# Motor-Z.net
KiCad netlist of a schematic drawn in Altium Designer
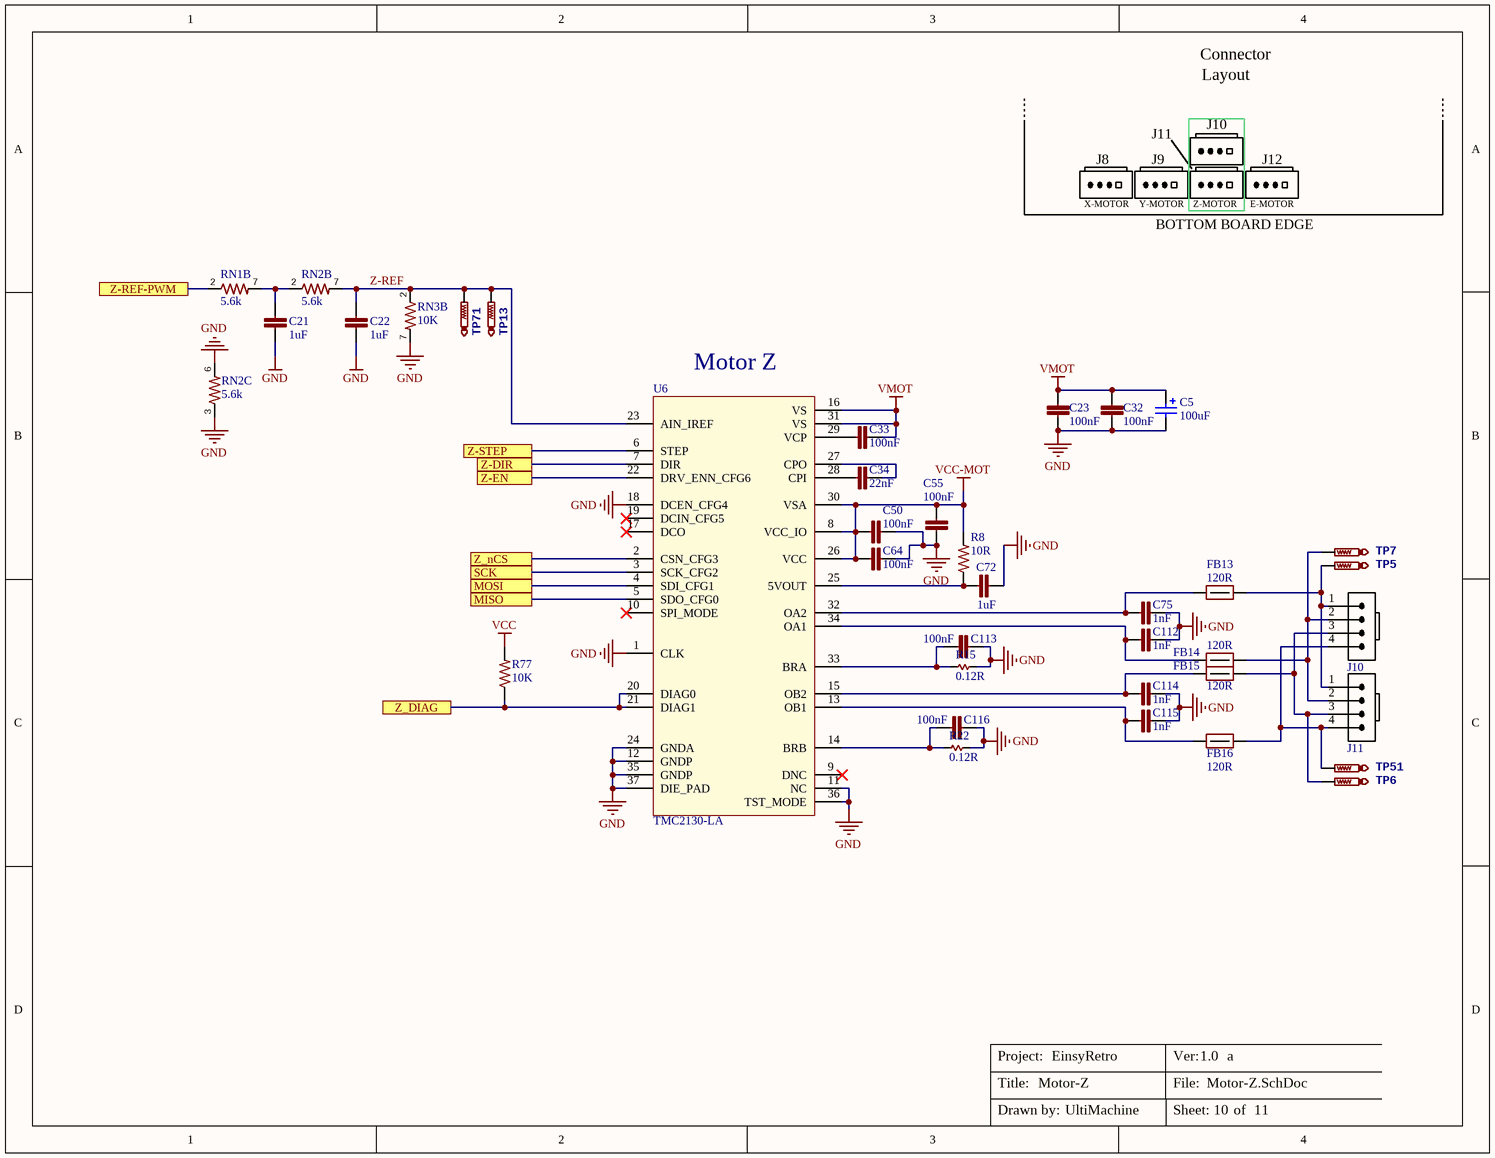
[diagram p0: Motor-Z.SchDoc]

(export (version "E")
  (design (tool "Eeschema 10.0.6"))
  (components
    (comp (ref "C5")
      (value "100uF")
      (footprint "CAP-ELEC-063063077")
      (description "CAP ALUM 100UF 35V 20% SMD")
      (fields (field (name "MANUFACTURER") "Nichicon") (field (name "TOLERANCE") "+/- 20%"))
      (libsource (lib "3Delight") (part "UWT1V101MCL1GS"))
    )
    (comp (ref "C21")
      (value "1uF")
      (footprint "C0402")
      (description "CAP CER 0402 1uF 6.3V 10% X5R")
      (fields (field (name "MANUFACTURER") "Murata") (field (name "TOLERANCE") "+/- 10%"))
      (libsource (lib "3Delight") (part "GRM155R60J105KE19D"))
    )
    (comp (ref "C22")
      (value "1uF")
      (footprint "C0402")
      (description "CAP CER 0402 1uF 6.3V 10% X5R")
      (fields (field (name "MANUFACTURER") "Murata") (field (name "TOLERANCE") "+/- 10%"))
      (libsource (lib "3Delight") (part "GRM155R60J105KE19D"))
    )
    (comp (ref "C23")
      (value "100nF")
      (footprint "C0603")
      (description "CAP CER 0603 100nF 50V 10% X7R")
      (fields (field (name "MANUFACTURER") "Kemet") (field (name "TOLERANCE") "+/- 10%"))
      (libsource (lib "") (part "C0603C104K5RACTU_1"))
    )
    (comp (ref "C32")
      (value "100nF")
      (footprint "C0603")
      (description "CAP CER 0603 100nF 50V 10% X7R")
      (fields (field (name "MANUFACTURER") "Kemet") (field (name "TOLERANCE") "+/- 10%"))
      (libsource (lib "") (part "C0603C104K5RACTU_1"))
    )
    (comp (ref "C33")
      (value "100nF")
      (footprint "C0603")
      (description "CAP CER 0603 100nF 50V 10% X7R")
      (fields (field (name "MANUFACTURER") "Kemet") (field (name "TOLERANCE") "+/- 10%"))
      (libsource (lib "") (part "C0603C104K5RACTU_2"))
    )
    (comp (ref "C34")
      (value "22nF")
      (footprint "C0402")
      (description "CAP CER 0402 22nF ±10% 50V X7R")
      (fields (field (name "MANUFACTURER") "YAGEO") (field (name "TOLERANCE") "+/- 10%"))
      (libsource (lib "3Delight") (part "GCM155R71H223KA55D"))
    )
    (comp (ref "C50")
      (value "100nF")
      (footprint "C0402")
      (description "CAP CER 0402 100nF 16V 10% X7R")
      (fields (field (name "MANUFACTURER") "Murata") (field (name "TOLERANCE") "+/- 10%"))
      (libsource (lib "") (part "GRM155R71C104KA88D_1"))
    )
    (comp (ref "C55")
      (value "100nF")
      (footprint "C0402")
      (description "CAP CER 0402 100nF 16V 10% X7R")
      (fields (field (name "MANUFACTURER") "Murata") (field (name "TOLERANCE") "+/- 10%"))
      (libsource (lib "3Delight") (part "GRM155R71C104KA88D"))
    )
    (comp (ref "C64")
      (value "100nF")
      (footprint "C0402")
      (description "CAP CER 0402 100nF 16V 10% X7R")
      (fields (field (name "MANUFACTURER") "Murata") (field (name "TOLERANCE") "+/- 10%"))
      (libsource (lib "") (part "GRM155R71C104KA88D_1"))
    )
    (comp (ref "C72")
      (value "1uF")
      (footprint "C0402")
      (description "CAP CER 0402 1uF 6.3V 10% X5R")
      (fields (field (name "MANUFACTURER") "Murata") (field (name "TOLERANCE") "+/- 10%"))
      (libsource (lib "") (part "GRM155R60J105KE19D_1"))
    )
    (comp (ref "C75")
      (value "1nF")
      (footprint "C0603")
      (description "CAP CER 0603  1nF 50v 10% X7R")
      (fields (field (name "MANUFACTURER") "Kemet") (field (name "TOLERANCE") "+/- 10%"))
      (libsource (lib "3Delight") (part "C0603C102K5RACTU"))
    )
    (comp (ref "C112")
      (value "1nF")
      (footprint "C0603")
      (description "CAP CER 0603  1nF 50v 10% X7R")
      (fields (field (name "MANUFACTURER") "Kemet") (field (name "TOLERANCE") "+/- 10%"))
      (libsource (lib "3Delight") (part "C0603C102K5RACTU"))
    )
    (comp (ref "C113")
      (value "100nF")
      (footprint "C0603")
      (description "CAP CER 0603 100nF 50V 10% X7R")
      (fields (field (name "MANUFACTURER") "Kemet") (field (name "TOLERANCE") "+/- 10%"))
      (libsource (lib "3Delight") (part "C0603C104K5RACTU"))
    )
    (comp (ref "C114")
      (value "1nF")
      (footprint "C0603")
      (description "CAP CER 0603  1nF 50v 10% X7R")
      (fields (field (name "MANUFACTURER") "Kemet") (field (name "TOLERANCE") "+/- 10%"))
      (libsource (lib "3Delight") (part "C0603C102K5RACTU"))
    )
    (comp (ref "C115")
      (value "1nF")
      (footprint "C0603")
      (description "CAP CER 0603  1nF 50v 10% X7R")
      (fields (field (name "MANUFACTURER") "Kemet") (field (name "TOLERANCE") "+/- 10%"))
      (libsource (lib "3Delight") (part "C0603C102K5RACTU"))
    )
    (comp (ref "C116")
      (value "100nF")
      (footprint "C0603")
      (description "CAP CER 0603 100nF 50V 10% X7R")
      (fields (field (name "MANUFACTURER") "Kemet") (field (name "TOLERANCE") "+/- 10%"))
      (libsource (lib "3Delight") (part "C0603C104K5RACTU"))
    )
    (comp (ref "FB13")
      (value "120R")
      (footprint "FB0603")
      (description "FERRITE BEAD 120 OHM 0603 1LN")
      (fields (field (name "MANUFACTURER") "Samsung") (field (name "PART") "FERRITE 120R 3A 0603"))
      (libsource (lib "Inductors") (part "FERRITE 120R 3A 0603"))
    )
    (comp (ref "FB14")
      (value "120R")
      (footprint "FB0603")
      (description "FERRITE BEAD 120 OHM 0603 1LN")
      (fields (field (name "MANUFACTURER") "Samsung") (field (name "PART") "FERRITE 120R 3A 0603"))
      (libsource (lib "Inductors") (part "FERRITE 120R 3A 0603"))
    )
    (comp (ref "FB15")
      (value "120R")
      (footprint "FB0603")
      (description "FERRITE BEAD 120 OHM 0603 1LN")
      (fields (field (name "MANUFACTURER") "Samsung") (field (name "PART") "FERRITE 120R 3A 0603"))
      (libsource (lib "Inductors") (part "FERRITE 120R 3A 0603"))
    )
    (comp (ref "FB16")
      (value "120R")
      (footprint "FB0603")
      (description "FERRITE BEAD 120 OHM 0603 1LN")
      (fields (field (name "MANUFACTURER") "Samsung") (field (name "PART") "FERRITE 120R 3A 0603"))
      (libsource (lib "Inductors") (part "FERRITE 120R 3A 0603"))
    )
    (comp (ref "J10")
      (value "Molex 0705430003")
      (footprint "4POL254 PIN-IN-PASTE")
      (description "Molex 4 Pin Clip Connector - Pin In Paste footprint")
      (libsource (lib "Connectors") (part "Molex 0705430003 PIP"))
    )
    (comp (ref "J11")
      (value "Molex 0705430003")
      (footprint "4POL254 PIN-IN-PASTE")
      (description "Molex 4 Pin Clip Connector - Pin In Paste footprint")
      (libsource (lib "Connectors") (part "Molex 0705430003 PIP"))
    )
    (comp (ref "R8")
      (value "10R")
      (footprint "R0402")
      (description "RES SMD 10 OHM 1% 1/16W 0402")
      (fields (field (name "MANUFACTURER") "Yageo") (field (name "TOLERANCE") "+/- 1%"))
      (libsource (lib "3Delight") (part "RC0402FR-0710RL"))
    )
    (comp (ref "R15")
      (value "0.12R")
      (footprint "R1206")
      (description "RES 0.12 OHM 1% 1/2W 1206")
      (fields (field (name "TOLERANCE") "+/- 1%"))
      (libsource (lib "Resistors") (part "0.12R 1% 1206"))
    )
    (comp (ref "R22")
      (value "0.12R")
      (footprint "R1206")
      (description "RES 0.12 OHM 1% 1/2W 1206")
      (fields (field (name "TOLERANCE") "+/- 1%"))
      (libsource (lib "Resistors") (part "0.12R 1% 1206"))
    )
    (comp (ref "R77")
      (value "10K")
      (footprint "R0402")
      (description "RES SMD 10K OHM 1% 1/16W 0402")
      (fields (field (name "MANUFACTURER") "Yageo") (field (name "PART") "10k 1% 0402"))
      (libsource (lib "3Delight") (part "RC0402FR-0710KP"))
    )
    (comp (ref "RN1")
      (value "5.6k")
      (footprint "CAY16")
      (description "RES ARRAY 4 RES 5.6K OHM 1206")
      (fields (field (name "MANUFACTURER") "Bourns") (field (name "TOLERANCE") "+/- 5%"))
      (libsource (lib "Resistors") (part "5.6k x 4 5% 1206"))
    )
    (comp (ref "RN2")
      (value "5.6k")
      (footprint "CAY16")
      (description "RES ARRAY 4 RES 5.6K OHM 1206")
      (fields (field (name "MANUFACTURER") "Bourns") (field (name "TOLERANCE") "+/- 5%"))
      (libsource (lib "Resistors") (part "5.6k x 4 5% 1206"))
    )
    (comp (ref "RN3")
      (value "10K")
      (footprint "CAY16")
      (description "RES ARRAY 4 RES 10K 1206 62.5mW 5%")
      (fields (field (name "MANUFACTURER") "Bourns") (field (name "TOLERANCE") "+/- 5%"))
      (libsource (lib "3Delight") (part "CAY16-103J4LF"))
    )
    (comp (ref "TP5")
      (value "TestPoint")
      (footprint "TP1-27")
      (description "Test Point")
      (libsource (lib "3Delight") (part "TestPoint"))
    )
    (comp (ref "TP6")
      (value "TestPoint")
      (footprint "TP1-27")
      (description "Test Point")
      (libsource (lib "3Delight") (part "TestPoint"))
    )
    (comp (ref "TP7")
      (value "TestPoint")
      (footprint "TP1-27")
      (description "Test Point")
      (libsource (lib "3Delight") (part "TestPoint"))
    )
    (comp (ref "TP13")
      (value "TestPoint")
      (footprint "TP1-27")
      (description "Test Point")
      (libsource (lib "") (part "TestPoint_1"))
    )
    (comp (ref "TP51")
      (value "TestPoint")
      (footprint "TP1-27")
      (description "Test Point")
      (libsource (lib "3Delight") (part "TestPoint"))
    )
    (comp (ref "TP71")
      (value "TestPoint")
      (footprint "TP1-27")
      (description "Test Point")
      (libsource (lib "") (part "TestPoint_1"))
    )
    (comp (ref "U6")
      (value "TMC2130-LA")
      (footprint "QFN36-50P500X600X900_HS-37N")
      (description "IC STEPPER MOTOR DVR SPI 36QFN")
      (fields (field (name "MANUFACTURER") "Trinamic") (field (name "PART") "TMC2130"))
      (libsource (lib "3Delight") (part "TMC2130-LA-T"))
    )
  )
  (nets
    (net (code "1") (name "/MISO") (class "Default")
      (node (ref "U6") (pin "5") (pinfunction "SDO_CFG0_5") (pintype "passive"))
    )
    (net (code "2") (name "/MOSI") (class "Default")
      (node (ref "U6") (pin "4") (pinfunction "SDI_CFG1_4") (pintype "passive"))
    )
    (net (code "3") (name "/SCK") (class "Default")
      (node (ref "U6") (pin "3") (pinfunction "SCK_CFG2_3") (pintype "passive"))
    )
    (net (code "4") (name "/Z-DIR") (class "Default")
      (node (ref "U6") (pin "7") (pinfunction "DIR_7") (pintype "passive"))
    )
    (net (code "5") (name "/Z-EN") (class "Default")
      (node (ref "U6") (pin "22") (pinfunction "DRV_ENN_CFG6_22") (pintype "passive"))
    )
    (net (code "6") (name "/Z-REF") (class "Default")
      (node (ref "C22") (pin "1") (pinfunction "1_1") (pintype "passive"))
      (node (ref "RN2") (pin "7") (pinfunction "2_7") (pintype "passive"))
      (node (ref "RN3") (pin "2") (pinfunction "1_2") (pintype "passive"))
      (node (ref "TP13") (pin "TP") (pinfunction "TP_TP") (pintype "passive"))
      (node (ref "TP71") (pin "TP") (pinfunction "TP_TP") (pintype "passive"))
      (node (ref "U6") (pin "23") (pinfunction "AIN_IREF_23") (pintype "passive"))
    )
    (net (code "7") (name "/Z-REF-PWM") (class "Default")
      (node (ref "RN1") (pin "2") (pinfunction "1_2") (pintype "passive"))
    )
    (net (code "8") (name "/Z-STEP") (class "Default")
      (node (ref "U6") (pin "6") (pinfunction "STEP_6") (pintype "passive"))
    )
    (net (code "9") (name "/Z_DIAG") (class "Default")
      (node (ref "R77") (pin "1") (pinfunction "1_1") (pintype "passive"))
      (node (ref "U6") (pin "20") (pinfunction "DIAG0_20") (pintype "passive"))
      (node (ref "U6") (pin "21") (pinfunction "DIAG1_21") (pintype "passive"))
    )
    (net (code "10") (name "/Z_nCS") (class "Default")
      (node (ref "U6") (pin "2") (pinfunction "CSN_CFG3_2") (pintype "passive"))
    )
    (net (code "11") (name "GND") (class "Default")
      (node (ref "C112") (pin "2") (pinfunction "2_2") (pintype "passive"))
      (node (ref "C113") (pin "1") (pinfunction "1_1") (pintype "passive"))
      (node (ref "C114") (pin "2") (pinfunction "2_2") (pintype "passive"))
      (node (ref "C115") (pin "2") (pinfunction "2_2") (pintype "passive"))
      (node (ref "C116") (pin "1") (pinfunction "1_1") (pintype "passive"))
      (node (ref "C21") (pin "2") (pinfunction "2_2") (pintype "passive"))
      (node (ref "C22") (pin "2") (pinfunction "2_2") (pintype "passive"))
      (node (ref "C23") (pin "1") (pinfunction "1_1") (pintype "passive"))
      (node (ref "C32") (pin "1") (pinfunction "1_1") (pintype "passive"))
      (node (ref "C5") (pin "2") (pinfunction "2_2") (pintype "passive"))
      (node (ref "C50") (pin "1") (pinfunction "1_1") (pintype "passive"))
      (node (ref "C55") (pin "1") (pinfunction "1_1") (pintype "passive"))
      (node (ref "C64") (pin "1") (pinfunction "1_1") (pintype "passive"))
      (node (ref "C72") (pin "2") (pinfunction "2_2") (pintype "passive"))
      (node (ref "C75") (pin "2") (pinfunction "2_2") (pintype "passive"))
      (node (ref "R15") (pin "2") (pinfunction "2_2") (pintype "passive"))
      (node (ref "R22") (pin "2") (pinfunction "2_2") (pintype "passive"))
      (node (ref "RN2") (pin "3") (pinfunction "1_3") (pintype "passive"))
      (node (ref "RN2") (pin "6") (pinfunction "2_6") (pintype "passive"))
      (node (ref "RN3") (pin "7") (pinfunction "2_7") (pintype "passive"))
      (node (ref "U6") (pin "1") (pinfunction "CLK_1") (pintype "passive"))
      (node (ref "U6") (pin "11") (pinfunction "NC_11") (pintype "passive"))
      (node (ref "U6") (pin "12") (pinfunction "GNDP_12") (pintype "passive"))
      (node (ref "U6") (pin "18") (pinfunction "DCEN_CFG4_18") (pintype "passive"))
      (node (ref "U6") (pin "24") (pinfunction "GNDA_24") (pintype "passive"))
      (node (ref "U6") (pin "35") (pinfunction "GNDP_35") (pintype "passive"))
      (node (ref "U6") (pin "36") (pinfunction "TST_MODE_36") (pintype "passive"))
      (node (ref "U6") (pin "37") (pinfunction "DIE_PAD_37") (pintype "passive"))
    )
    (net (code "12") (name "Net-(FB13-Pad2)") (class "Default")
      (node (ref "FB13") (pin "2") (pinfunction "2_2") (pintype "passive"))
      (node (ref "J10") (pin "1") (pinfunction "1_1") (pintype "passive"))
      (node (ref "J11") (pin "1") (pinfunction "1_1") (pintype "passive"))
      (node (ref "TP5") (pin "TP") (pinfunction "TP_TP") (pintype "passive"))
    )
    (net (code "13") (name "Net-(FB14-Pad2)") (class "Default")
      (node (ref "FB14") (pin "2") (pinfunction "2_2") (pintype "passive"))
      (node (ref "J10") (pin "2") (pinfunction "2_2") (pintype "passive"))
      (node (ref "J11") (pin "2") (pinfunction "2_2") (pintype "passive"))
      (node (ref "TP7") (pin "TP") (pinfunction "TP_TP") (pintype "passive"))
    )
    (net (code "14") (name "Net-(FB15-Pad2)") (class "Default")
      (node (ref "FB15") (pin "2") (pinfunction "2_2") (pintype "passive"))
      (node (ref "J10") (pin "3") (pinfunction "3_3") (pintype "passive"))
      (node (ref "J11") (pin "3") (pinfunction "3_3") (pintype "passive"))
      (node (ref "TP6") (pin "TP") (pinfunction "TP_TP") (pintype "passive"))
    )
    (net (code "15") (name "Net-(FB16-Pad2)") (class "Default")
      (node (ref "FB16") (pin "2") (pinfunction "2_2") (pintype "passive"))
      (node (ref "J10") (pin "4") (pinfunction "4_4") (pintype "passive"))
      (node (ref "J11") (pin "4") (pinfunction "4_4") (pintype "passive"))
      (node (ref "TP51") (pin "TP") (pinfunction "TP_TP") (pintype "passive"))
    )
    (net (code "16") (name "Net-(RN1B-2)") (class "Default")
      (node (ref "C21") (pin "1") (pinfunction "1_1") (pintype "passive"))
      (node (ref "RN1") (pin "7") (pinfunction "2_7") (pintype "passive"))
      (node (ref "RN2") (pin "2") (pinfunction "1_2") (pintype "passive"))
    )
    (net (code "17") (name "Net-(U6-5VOUT)") (class "Default")
      (node (ref "C72") (pin "1") (pinfunction "1_1") (pintype "passive"))
      (node (ref "R8") (pin "1") (pinfunction "1_1") (pintype "passive"))
      (node (ref "U6") (pin "25") (pinfunction "5VOUT_25") (pintype "passive"))
    )
    (net (code "18") (name "Net-(U6-BRA)") (class "Default")
      (node (ref "C113") (pin "2") (pinfunction "2_2") (pintype "passive"))
      (node (ref "R15") (pin "1") (pinfunction "1_1") (pintype "passive"))
      (node (ref "U6") (pin "33") (pinfunction "BRA_33") (pintype "passive"))
    )
    (net (code "19") (name "Net-(U6-BRB)") (class "Default")
      (node (ref "C116") (pin "2") (pinfunction "2_2") (pintype "passive"))
      (node (ref "R22") (pin "1") (pinfunction "1_1") (pintype "passive"))
      (node (ref "U6") (pin "14") (pinfunction "BRB_14") (pintype "passive"))
    )
    (net (code "20") (name "Net-(U6-CPI)") (class "Default")
      (node (ref "C34") (pin "1") (pinfunction "1_1") (pintype "passive"))
      (node (ref "U6") (pin "28") (pinfunction "CPI_28") (pintype "passive"))
    )
    (net (code "21") (name "Net-(U6-CPO)") (class "Default")
      (node (ref "C34") (pin "2") (pinfunction "2_2") (pintype "passive"))
      (node (ref "U6") (pin "27") (pinfunction "CPO_27") (pintype "passive"))
    )
    (net (code "22") (name "Net-(U6-OA1)") (class "Default")
      (node (ref "C112") (pin "1") (pinfunction "1_1") (pintype "passive"))
      (node (ref "FB14") (pin "1") (pinfunction "1_1") (pintype "passive"))
      (node (ref "U6") (pin "34") (pinfunction "OA1_34") (pintype "passive"))
    )
    (net (code "23") (name "Net-(U6-OA2)") (class "Default")
      (node (ref "C75") (pin "1") (pinfunction "1_1") (pintype "passive"))
      (node (ref "FB13") (pin "1") (pinfunction "1_1") (pintype "passive"))
      (node (ref "U6") (pin "32") (pinfunction "OA2_32") (pintype "passive"))
    )
    (net (code "24") (name "Net-(U6-OB1)") (class "Default")
      (node (ref "C115") (pin "1") (pinfunction "1_1") (pintype "passive"))
      (node (ref "FB16") (pin "1") (pinfunction "1_1") (pintype "passive"))
      (node (ref "U6") (pin "13") (pinfunction "OB1_13") (pintype "passive"))
    )
    (net (code "25") (name "Net-(U6-OB2)") (class "Default")
      (node (ref "C114") (pin "1") (pinfunction "1_1") (pintype "passive"))
      (node (ref "FB15") (pin "1") (pinfunction "1_1") (pintype "passive"))
      (node (ref "U6") (pin "15") (pinfunction "OB2_15") (pintype "passive"))
    )
    (net (code "26") (name "Net-(U6-VCP)") (class "Default")
      (node (ref "C33") (pin "1") (pinfunction "1_1") (pintype "passive"))
      (node (ref "U6") (pin "29") (pinfunction "VCP_29") (pintype "passive"))
    )
    (net (code "27") (name "VCC") (class "Default")
      (node (ref "R77") (pin "2") (pinfunction "2_2") (pintype "passive"))
    )
    (net (code "28") (name "VCC-MOT") (class "Default")
      (node (ref "C50") (pin "2") (pinfunction "2_2") (pintype "passive"))
      (node (ref "C55") (pin "2") (pinfunction "2_2") (pintype "passive"))
      (node (ref "C64") (pin "2") (pinfunction "2_2") (pintype "passive"))
      (node (ref "R8") (pin "2") (pinfunction "2_2") (pintype "passive"))
      (node (ref "U6") (pin "26") (pinfunction "VCC_26") (pintype "passive"))
      (node (ref "U6") (pin "30") (pinfunction "VSA_30") (pintype "passive"))
      (node (ref "U6") (pin "8") (pinfunction "VCC_IO_8") (pintype "passive"))
    )
    (net (code "29") (name "VMOT") (class "Default")
      (node (ref "C23") (pin "2") (pinfunction "2_2") (pintype "passive"))
      (node (ref "C32") (pin "2") (pinfunction "2_2") (pintype "passive"))
      (node (ref "C33") (pin "2") (pinfunction "2_2") (pintype "passive"))
      (node (ref "C5") (pin "1") (pinfunction "1_1") (pintype "passive"))
      (node (ref "U6") (pin "16") (pinfunction "VS_16") (pintype "passive"))
      (node (ref "U6") (pin "31") (pinfunction "VS_31") (pintype "passive"))
    )
    (net (code "30") (name "unconnected-(U6-DCIN_CFG5-Pad19)") (class "Default")
      (node (ref "U6") (pin "19") (pinfunction "DCIN_CFG5_19") (pintype "passive+no_connect"))
    )
    (net (code "31") (name "unconnected-(U6-DCO-Pad17)") (class "Default")
      (node (ref "U6") (pin "17") (pinfunction "DCO_17") (pintype "passive+no_connect"))
    )
    (net (code "32") (name "unconnected-(U6-DNC-Pad9)") (class "Default")
      (node (ref "U6") (pin "9") (pinfunction "DNC_9") (pintype "passive+no_connect"))
    )
    (net (code "33") (name "unconnected-(U6-SPI_MODE-Pad10)") (class "Default")
      (node (ref "U6") (pin "10") (pinfunction "SPI_MODE_10") (pintype "passive+no_connect"))
    )
  )
)
